# Copy_of_MCU_64.net
KiCad netlist of a schematic drawn in Altium Designer
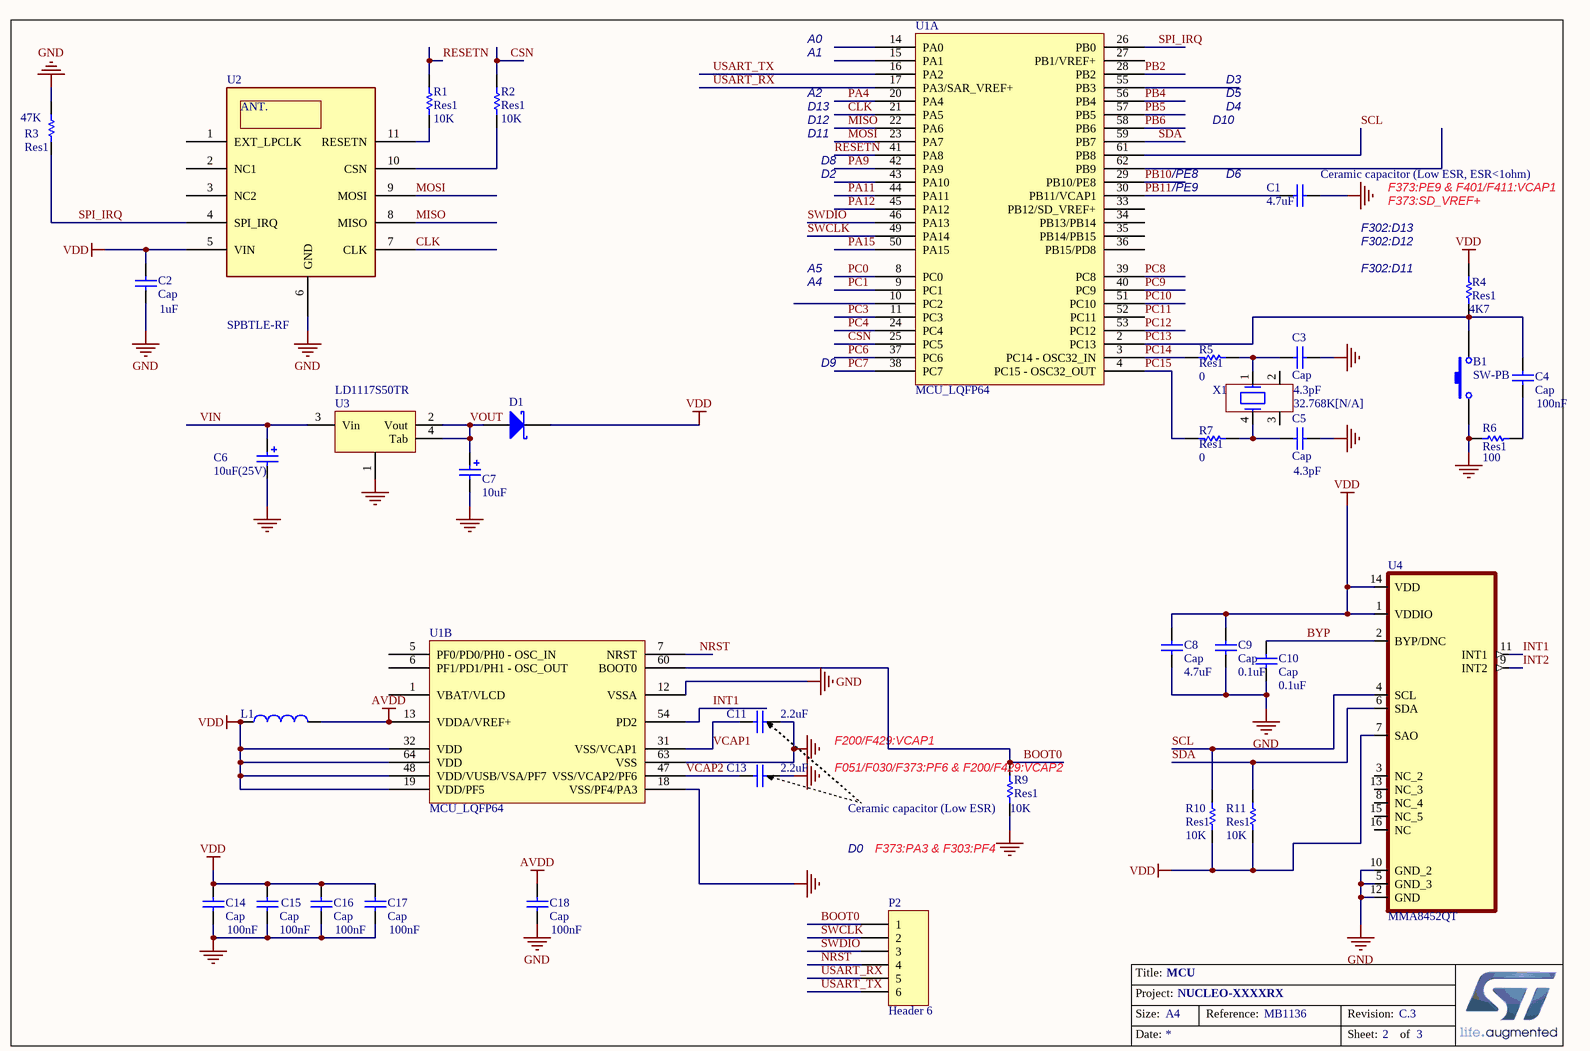
[diagram p0: Copy of MCU_64.SchDoc]

(export (version "E")
  (design (tool "Eeschema 10.0.6"))
  (components
    (comp (ref "B1")
      (value "SW-PB")
      (footprint "SPST-2")
      (description "Switch")
      (fields (field (name "PUBLISHER") "Altium Limited"))
      (libsource (lib "Gen_Devices") (part "SW-PB"))
    )
    (comp (ref "C1")
      (value "4.7uF")
      (footprint "TAN-A")
      (description "Capacitor,4.7uF,25V, X7R,10%,1206,YAGEO")
      (libsource (lib "MCD_TOOLS") (part "Cap_2.2uF_X7R_10%_0805"))
    )
    (comp (ref "C2")
      (value "Cap")
      (footprint "0603[IMP]-CAP")
      (description "Capacitor")
      (fields (field (name "ALTIUM_VALUE") "1uF"))
      (libsource (lib "Gen_Devices") (part "Cap"))
    )
    (comp (ref "C3")
      (value "Cap")
      (footprint "0603[IMP]-CAP")
      (description "Capacitor")
      (fields (field (name "ALTIUM_VALUE") "4.3pF"))
      (libsource (lib "Gen_Devices") (part "Cap"))
    )
    (comp (ref "C4")
      (value "Cap")
      (footprint "0603[IMP]-CAP")
      (description "Capacitor")
      (fields (field (name "ALTIUM_VALUE") "100nF"))
      (libsource (lib "Gen_Devices") (part "Cap"))
    )
    (comp (ref "C5")
      (value "Cap")
      (footprint "0603[IMP]-CAP")
      (description "Capacitor")
      (fields (field (name "ALTIUM_VALUE") "4.3pF"))
      (libsource (lib "Gen_Devices") (part "Cap"))
    )
    (comp (ref "C6")
      (value "10uF(25V)")
      (footprint "TAN-B")
      (description "Polarized Capacitor (Radial)")
      (fields (field (name "PUBLISHER") "Altium Limited"))
      (libsource (lib "Gen_Devices") (part "Cap Pol1"))
    )
    (comp (ref "C7")
      (value "10uF")
      (footprint "TAN-A")
      (description "Polarized Capacitor (Radial)")
      (fields (field (name "PUBLISHER") "Altium Limited"))
      (libsource (lib "Gen_Devices") (part "Cap Pol1"))
    )
    (comp (ref "C8")
      (value "Cap")
      (footprint "0603[IMP]-CAP")
      (description "Capacitor")
      (fields (field (name "ALTIUM_VALUE") "4.7uF"))
      (libsource (lib "Gen_Devices") (part "Cap"))
    )
    (comp (ref "C9")
      (value "Cap")
      (footprint "0603[IMP]-CAP")
      (description "Capacitor")
      (fields (field (name "ALTIUM_VALUE") "0.1uF"))
      (libsource (lib "Gen_Devices") (part "Cap"))
    )
    (comp (ref "C10")
      (value "Cap")
      (footprint "0603[IMP]-CAP")
      (description "Capacitor")
      (fields (field (name "ALTIUM_VALUE") "0.1uF"))
      (libsource (lib "Gen_Devices") (part "Cap"))
    )
    (comp (ref "C11")
      (value "2.2uF")
      (footprint "TAN-A")
      (description "Capacitor,2.2uF,16V, X7R,10%,0805,YAGEO")
      (libsource (lib "MCD_TOOLS") (part "Cap_2.2uF_X7R_10%_0805"))
    )
    (comp (ref "C13")
      (value "2.2uF")
      (footprint "TAN-A")
      (description "Capacitor,2.2uF,16V, X7R,10%,0805,YAGEO")
      (libsource (lib "MCD_TOOLS") (part "Cap_2.2uF_X7R_10%_0805"))
    )
    (comp (ref "C14")
      (value "Cap")
      (footprint "0603[IMP]-CAP")
      (description "Capacitor")
      (fields (field (name "ALTIUM_VALUE") "100nF"))
      (libsource (lib "Gen_Devices") (part "Cap"))
    )
    (comp (ref "C15")
      (value "Cap")
      (footprint "0603[IMP]-CAP")
      (description "Capacitor")
      (fields (field (name "ALTIUM_VALUE") "100nF"))
      (libsource (lib "Gen_Devices") (part "Cap"))
    )
    (comp (ref "C16")
      (value "Cap")
      (footprint "0603[IMP]-CAP")
      (description "Capacitor")
      (fields (field (name "ALTIUM_VALUE") "100nF"))
      (libsource (lib "Gen_Devices") (part "Cap"))
    )
    (comp (ref "C17")
      (value "Cap")
      (footprint "0603[IMP]-CAP")
      (description "Capacitor")
      (fields (field (name "ALTIUM_VALUE") "100nF"))
      (libsource (lib "Gen_Devices") (part "Cap"))
    )
    (comp (ref "C18")
      (value "Cap")
      (footprint "0603[IMP]-CAP")
      (description "Capacitor")
      (fields (field (name "ALTIUM_VALUE") "100nF"))
      (libsource (lib "Gen_Devices") (part "Cap"))
    )
    (comp (ref "D1")
      (value "~")
      (footprint "SMB")
      (description "Schottky Diode")
      (fields (field (name "PUBLISHER") "Altium Limited"))
      (libsource (lib "Gen_Devices") (part "D Schottky"))
    )
    (comp (ref "L1")
      (value "~")
      (footprint "0603[IMP]-CAP")
      (description "Inductor")
      (fields (field (name "PUBLISHER") "Altium Limited"))
      (libsource (lib "Miscellaneous Devices") (part "Inductor"))
    )
    (comp (ref "P2")
      (value "Header 6")
      (footprint "HDR1X6")
      (description "Header, 6-Pin")
      (fields (field (name "PUBLISHER") "Altium Limited"))
      (libsource (lib "Gen_Connectors") (part "Header 6"))
    )
    (comp (ref "R1")
      (value "Res1")
      (footprint "0603[IMP]-RES")
      (description "Resistor")
      (fields (field (name "ALTIUM_VALUE") "10K") (field (name "PUBLISHER") "Altium Limited"))
      (libsource (lib "Gen_Devices") (part "Res1"))
    )
    (comp (ref "R2")
      (value "Res1")
      (footprint "0603[IMP]-RES")
      (description "Resistor")
      (fields (field (name "ALTIUM_VALUE") "10K") (field (name "PUBLISHER") "Altium Limited"))
      (libsource (lib "Gen_Devices") (part "Res1"))
    )
    (comp (ref "R3")
      (value "Res1")
      (footprint "0603[IMP]-RES")
      (description "Resistor")
      (fields (field (name "ALTIUM_VALUE") "47K") (field (name "PUBLISHER") "Altium Limited"))
      (libsource (lib "Gen_Devices") (part "Res1"))
    )
    (comp (ref "R4")
      (value "Res1")
      (footprint "0603[IMP]-RES")
      (description "Resistor")
      (fields (field (name "ALTIUM_VALUE") "4K7") (field (name "PUBLISHER") "Altium Limited"))
      (libsource (lib "Gen_Devices") (part "Res1"))
    )
    (comp (ref "R5")
      (value "Res1")
      (footprint "0603[IMP]-RES")
      (description "Resistor")
      (fields (field (name "ALTIUM_VALUE") "0") (field (name "PUBLISHER") "Altium Limited"))
      (libsource (lib "Gen_Devices") (part "Res1"))
    )
    (comp (ref "R6")
      (value "Res1")
      (footprint "0603[IMP]-RES")
      (description "Resistor")
      (fields (field (name "ALTIUM_VALUE") "100") (field (name "PUBLISHER") "Altium Limited"))
      (libsource (lib "Gen_Devices") (part "Res1"))
    )
    (comp (ref "R7")
      (value "Res1")
      (footprint "0603[IMP]-RES")
      (description "Resistor")
      (fields (field (name "ALTIUM_VALUE") "0") (field (name "PUBLISHER") "Altium Limited"))
      (libsource (lib "Gen_Devices") (part "Res1"))
    )
    (comp (ref "R9")
      (value "Res1")
      (footprint "0603[IMP]-RES")
      (description "Resistor")
      (fields (field (name "ALTIUM_VALUE") "10K") (field (name "PUBLISHER") "Altium Limited"))
      (libsource (lib "Gen_Devices") (part "Res1"))
    )
    (comp (ref "R10")
      (value "Res1")
      (footprint "0603[IMP]-RES")
      (description "Resistor")
      (fields (field (name "ALTIUM_VALUE") "10K") (field (name "PUBLISHER") "Altium Limited"))
      (libsource (lib "Gen_Devices") (part "Res1"))
    )
    (comp (ref "R11")
      (value "Res1")
      (footprint "0603[IMP]-RES")
      (description "Resistor")
      (fields (field (name "ALTIUM_VALUE") "10K") (field (name "PUBLISHER") "Altium Limited"))
      (libsource (lib "Gen_Devices") (part "Res1"))
    )
    (comp (ref "U1")
      (value "MCU_LQFP64")
      (footprint "LQFP64")
      (libsource (lib "Nucleo_64") (part "MCU_LQFP64"))
    )
    (comp (ref "U2")
      (value "SPBTLE-RF")
      (footprint "SPBTLE-RF")
      (description "Module BlueNRG")
      (libsource (lib "KNOCKLET_BRAC") (part "SPBTLE-RF"))
    )
    (comp (ref "U3")
      (value "LD1117S50TR")
      (footprint "SOT223_N")
      (libsource (lib "Gen_Devices") (part "LD1117"))
    )
    (comp (ref "U4")
      (value "MMA8452QT")
      (footprint "MMA8452QT")
      (libsource (lib "Accelerometres") (part "MMA8452QT"))
    )
    (comp (ref "X1")
      (value "32.768K[N/A]")
      (footprint "Quartz_ABS25")
      (libsource (lib "KNOCKLET_BRAC") (part "MC306"))
    )
  )
  (nets
    (net (code "1") (name "/BOOT0") (class "Default")
      (node (ref "P2") (pin "1") (pinfunction "1_1") (pintype "passive"))
      (node (ref "R9") (pin "1") (pinfunction "1_1") (pintype "passive"))
      (node (ref "U1") (pin "60") (pinfunction "BOOT0_60") (pintype "passive"))
    )
    (net (code "2") (name "/BYP") (class "Default")
      (node (ref "C10") (pin "2") (pinfunction "2_2") (pintype "passive"))
      (node (ref "U4") (pin "2") (pinfunction "BYP/DNC_2") (pintype "passive"))
    )
    (net (code "3") (name "/CLK") (class "Default")
      (node (ref "U1") (pin "21") (pinfunction "PA5_21") (pintype "passive"))
      (node (ref "U2") (pin "7") (pinfunction "CLK_7") (pintype "passive"))
    )
    (net (code "4") (name "/CSN") (class "Default")
      (node (ref "R2") (pin "2") (pinfunction "2_2") (pintype "passive"))
      (node (ref "U1") (pin "25") (pinfunction "PC5_25") (pintype "passive"))
    )
    (net (code "5") (name "/INT1") (class "Default")
      (node (ref "U1") (pin "54") (pinfunction "PD2_54") (pintype "passive"))
      (node (ref "U4") (pin "11") (pinfunction "INT1_11") (pintype "output"))
    )
    (net (code "6") (name "/INT2") (class "Default")
      (node (ref "U4") (pin "9") (pinfunction "INT2_9") (pintype "output"))
    )
    (net (code "7") (name "/MISO") (class "Default")
      (node (ref "U1") (pin "22") (pinfunction "PA6_22") (pintype "passive"))
      (node (ref "U2") (pin "8") (pinfunction "MISO_8") (pintype "passive"))
    )
    (net (code "8") (name "/MOSI") (class "Default")
      (node (ref "U1") (pin "23") (pinfunction "PA7_23") (pintype "passive"))
      (node (ref "U2") (pin "9") (pinfunction "MOSI_9") (pintype "passive"))
    )
    (net (code "9") (name "/NRST") (class "Default")
      (node (ref "P2") (pin "4") (pinfunction "4_4") (pintype "passive"))
      (node (ref "U1") (pin "7") (pinfunction "NRST_7") (pintype "passive"))
    )
    (net (code "10") (name "/PA4") (class "Default")
      (node (ref "U1") (pin "20") (pinfunction "PA4_20") (pintype "passive"))
    )
    (net (code "11") (name "/PA9") (class "Default")
      (node (ref "U1") (pin "42") (pinfunction "PA9_42") (pintype "passive"))
    )
    (net (code "12") (name "/PA11") (class "Default")
      (node (ref "U1") (pin "44") (pinfunction "PA11_44") (pintype "passive"))
    )
    (net (code "13") (name "/PA12") (class "Default")
      (node (ref "U1") (pin "45") (pinfunction "PA12_45") (pintype "passive"))
    )
    (net (code "14") (name "/PA15") (class "Default")
      (node (ref "U1") (pin "50") (pinfunction "PA15_50") (pintype "passive"))
    )
    (net (code "15") (name "/PB2") (class "Default")
      (node (ref "U1") (pin "28") (pinfunction "PB2_28") (pintype "passive"))
    )
    (net (code "16") (name "/PB4") (class "Default")
      (node (ref "U1") (pin "56") (pinfunction "PB4_56") (pintype "passive"))
    )
    (net (code "17") (name "/PB5") (class "Default")
      (node (ref "U1") (pin "57") (pinfunction "PB5_57") (pintype "passive"))
    )
    (net (code "18") (name "/PB6") (class "Default")
      (node (ref "U1") (pin "58") (pinfunction "PB6_58") (pintype "passive"))
    )
    (net (code "19") (name "/PB10") (class "Default")
      (node (ref "U1") (pin "29") (pinfunction "PB10/PE8_29") (pintype "passive"))
    )
    (net (code "20") (name "/PB11") (class "Default")
      (node (ref "C1") (pin "1") (pinfunction "1_1") (pintype "passive"))
      (node (ref "U1") (pin "30") (pinfunction "PB11/VCAP1_30") (pintype "passive"))
    )
    (net (code "21") (name "/PC0") (class "Default")
      (node (ref "U1") (pin "8") (pinfunction "PC0_8") (pintype "passive"))
    )
    (net (code "22") (name "/PC1") (class "Default")
      (node (ref "U1") (pin "9") (pinfunction "PC1_9") (pintype "passive"))
    )
    (net (code "23") (name "/PC3") (class "Default")
      (node (ref "U1") (pin "11") (pinfunction "PC3_11") (pintype "passive"))
    )
    (net (code "24") (name "/PC4") (class "Default")
      (node (ref "U1") (pin "24") (pinfunction "PC4_24") (pintype "passive"))
    )
    (net (code "25") (name "/PC6") (class "Default")
      (node (ref "U1") (pin "37") (pinfunction "PC6_37") (pintype "passive"))
    )
    (net (code "26") (name "/PC7") (class "Default")
      (node (ref "U1") (pin "38") (pinfunction "PC7_38") (pintype "passive"))
    )
    (net (code "27") (name "/PC8") (class "Default")
      (node (ref "U1") (pin "39") (pinfunction "PC8_39") (pintype "passive"))
    )
    (net (code "28") (name "/PC9") (class "Default")
      (node (ref "U1") (pin "40") (pinfunction "PC9_40") (pintype "passive"))
    )
    (net (code "29") (name "/PC10") (class "Default")
      (node (ref "U1") (pin "51") (pinfunction "PC10_51") (pintype "passive"))
    )
    (net (code "30") (name "/PC11") (class "Default")
      (node (ref "U1") (pin "52") (pinfunction "PC11_52") (pintype "passive"))
    )
    (net (code "31") (name "/PC12") (class "Default")
      (node (ref "U1") (pin "53") (pinfunction "PC12_53") (pintype "passive"))
    )
    (net (code "32") (name "/PC13") (class "Default")
      (node (ref "B1") (pin "2") (pinfunction "2_2") (pintype "passive"))
      (node (ref "C4") (pin "2") (pinfunction "2_2") (pintype "passive"))
      (node (ref "R4") (pin "1") (pinfunction "1_1") (pintype "passive"))
      (node (ref "U1") (pin "2") (pinfunction "PC13_2") (pintype "passive"))
    )
    (net (code "33") (name "/PC14") (class "Default")
      (node (ref "R5") (pin "1") (pinfunction "1_1") (pintype "passive"))
      (node (ref "U1") (pin "3") (pinfunction "PC14_-_OSC32_IN_3") (pintype "passive"))
    )
    (net (code "34") (name "/PC15") (class "Default")
      (node (ref "R7") (pin "1") (pinfunction "1_1") (pintype "passive"))
      (node (ref "U1") (pin "4") (pinfunction "PC15_-_OSC32_OUT_4") (pintype "passive"))
    )
    (net (code "35") (name "/RESETN") (class "Default")
      (node (ref "R1") (pin "2") (pinfunction "2_2") (pintype "passive"))
      (node (ref "U1") (pin "41") (pinfunction "PA8_41") (pintype "passive"))
    )
    (net (code "36") (name "/SCL") (class "Default")
      (node (ref "R10") (pin "2") (pinfunction "2_2") (pintype "passive"))
      (node (ref "U1") (pin "61") (pinfunction "PB8_61") (pintype "passive"))
      (node (ref "U4") (pin "4") (pinfunction "SCL_4") (pintype "passive"))
    )
    (net (code "37") (name "/SDA") (class "Default")
      (node (ref "R11") (pin "2") (pinfunction "2_2") (pintype "passive"))
      (node (ref "U1") (pin "59") (pinfunction "PB7_59") (pintype "passive"))
      (node (ref "U4") (pin "6") (pinfunction "SDA_6") (pintype "passive"))
    )
    (net (code "38") (name "/SPI_IRQ") (class "Default")
      (node (ref "R3") (pin "1") (pinfunction "1_1") (pintype "passive"))
      (node (ref "U1") (pin "26") (pinfunction "PB0_26") (pintype "passive"))
      (node (ref "U2") (pin "4") (pinfunction "SPI_IRQ_4") (pintype "passive"))
    )
    (net (code "39") (name "/SWCLK") (class "Default")
      (node (ref "P2") (pin "2") (pinfunction "2_2") (pintype "passive"))
      (node (ref "U1") (pin "49") (pinfunction "PA14_49") (pintype "passive"))
    )
    (net (code "40") (name "/SWDIO") (class "Default")
      (node (ref "P2") (pin "3") (pinfunction "3_3") (pintype "passive"))
      (node (ref "U1") (pin "46") (pinfunction "PA13_46") (pintype "passive"))
    )
    (net (code "41") (name "/USART_RX") (class "Default")
      (node (ref "P2") (pin "5") (pinfunction "5_5") (pintype "passive"))
      (node (ref "U1") (pin "17") (pinfunction "PA3/SAR_VREF+_17") (pintype "passive"))
    )
    (net (code "42") (name "/USART_TX") (class "Default")
      (node (ref "P2") (pin "6") (pinfunction "6_6") (pintype "passive"))
      (node (ref "U1") (pin "16") (pinfunction "PA2_16") (pintype "passive"))
    )
    (net (code "43") (name "/VCAP1") (class "Default")
      (node (ref "C11") (pin "1") (pinfunction "1_1") (pintype "passive"))
      (node (ref "U1") (pin "31") (pinfunction "VSS/VCAP1_31") (pintype "passive"))
    )
    (net (code "44") (name "/VCAP2") (class "Default")
      (node (ref "C13") (pin "1") (pinfunction "1_1") (pintype "passive"))
      (node (ref "U1") (pin "47") (pinfunction "VSS/VCAP2/PF6_47") (pintype "passive"))
    )
    (net (code "45") (name "/VIN") (class "Default")
      (node (ref "C6") (pin "1") (pinfunction "1_1") (pintype "passive"))
      (node (ref "U3") (pin "3") (pinfunction "Vin_3") (pintype "power_in"))
    )
    (net (code "46") (name "/VOUT") (class "Default")
      (node (ref "C7") (pin "1") (pinfunction "1_1") (pintype "passive"))
      (node (ref "D1") (pin "1") (pinfunction "A_1") (pintype "passive"))
      (node (ref "U3") (pin "2") (pinfunction "Vout_2") (pintype "power_in"))
      (node (ref "U3") (pin "4") (pinfunction "Tab_4") (pintype "power_in"))
    )
    (net (code "47") (name "AVDD") (class "Default")
      (node (ref "C18") (pin "1") (pinfunction "1_1") (pintype "passive"))
      (node (ref "L1") (pin "2") (pinfunction "2_2") (pintype "passive"))
      (node (ref "U1") (pin "13") (pinfunction "VDDA/VREF+_13") (pintype "passive"))
    )
    (net (code "48") (name "GND") (class "Default")
      (node (ref "B1") (pin "1") (pinfunction "1_1") (pintype "passive"))
      (node (ref "C1") (pin "2") (pinfunction "2_2") (pintype "passive"))
      (node (ref "C10") (pin "1") (pinfunction "1_1") (pintype "passive"))
      (node (ref "C11") (pin "2") (pinfunction "2_2") (pintype "passive"))
      (node (ref "C13") (pin "2") (pinfunction "2_2") (pintype "passive"))
      (node (ref "C14") (pin "2") (pinfunction "2_2") (pintype "passive"))
      (node (ref "C15") (pin "2") (pinfunction "2_2") (pintype "passive"))
      (node (ref "C16") (pin "2") (pinfunction "2_2") (pintype "passive"))
      (node (ref "C17") (pin "2") (pinfunction "2_2") (pintype "passive"))
      (node (ref "C18") (pin "2") (pinfunction "2_2") (pintype "passive"))
      (node (ref "C2") (pin "1") (pinfunction "1_1") (pintype "passive"))
      (node (ref "C3") (pin "1") (pinfunction "1_1") (pintype "passive"))
      (node (ref "C5") (pin "1") (pinfunction "1_1") (pintype "passive"))
      (node (ref "C6") (pin "2") (pinfunction "2_2") (pintype "passive"))
      (node (ref "C7") (pin "2") (pinfunction "2_2") (pintype "passive"))
      (node (ref "C8") (pin "1") (pinfunction "1_1") (pintype "passive"))
      (node (ref "C9") (pin "1") (pinfunction "1_1") (pintype "passive"))
      (node (ref "R3") (pin "2") (pinfunction "2_2") (pintype "passive"))
      (node (ref "R6") (pin "1") (pinfunction "1_1") (pintype "passive"))
      (node (ref "R9") (pin "2") (pinfunction "2_2") (pintype "passive"))
      (node (ref "U1") (pin "12") (pinfunction "VSSA_12") (pintype "passive"))
      (node (ref "U1") (pin "18") (pinfunction "VSS/PF4/PA3_18") (pintype "passive"))
      (node (ref "U1") (pin "63") (pinfunction "VSS_63") (pintype "passive"))
      (node (ref "U2") (pin "6") (pinfunction "GND_6") (pintype "passive"))
      (node (ref "U3") (pin "1") (pintype "passive"))
      (node (ref "U4") (pin "10") (pinfunction "GND_2_10") (pintype "passive"))
      (node (ref "U4") (pin "12") (pinfunction "GND_12") (pintype "passive"))
      (node (ref "U4") (pin "5") (pinfunction "GND_3_5") (pintype "passive"))
    )
    (net (code "49") (name "Net-(C3-Pad2)") (class "Default")
      (node (ref "C3") (pin "2") (pinfunction "2_2") (pintype "passive"))
      (node (ref "R5") (pin "2") (pinfunction "2_2") (pintype "passive"))
      (node (ref "X1") (pin "1") (pinfunction "1_1") (pintype "passive"))
    )
    (net (code "50") (name "Net-(C4-Pad1)") (class "Default")
      (node (ref "C4") (pin "1") (pinfunction "1_1") (pintype "passive"))
      (node (ref "R6") (pin "2") (pinfunction "2_2") (pintype "passive"))
    )
    (net (code "51") (name "Net-(C5-Pad2)") (class "Default")
      (node (ref "C5") (pin "2") (pinfunction "2_2") (pintype "passive"))
      (node (ref "R7") (pin "2") (pinfunction "2_2") (pintype "passive"))
      (node (ref "X1") (pin "4") (pinfunction "4_4") (pintype "passive"))
    )
    (net (code "52") (name "Net-(U2-CSN)") (class "Default")
      (node (ref "R2") (pin "1") (pinfunction "1_1") (pintype "passive"))
      (node (ref "U2") (pin "10") (pinfunction "CSN_10") (pintype "passive"))
    )
    (net (code "53") (name "Net-(U2-RESETN)") (class "Default")
      (node (ref "R1") (pin "1") (pinfunction "1_1") (pintype "passive"))
      (node (ref "U2") (pin "11") (pinfunction "RESETN_11") (pintype "passive"))
    )
    (net (code "54") (name "VDD") (class "Default")
      (node (ref "C14") (pin "1") (pinfunction "1_1") (pintype "passive"))
      (node (ref "C15") (pin "1") (pinfunction "1_1") (pintype "passive"))
      (node (ref "C16") (pin "1") (pinfunction "1_1") (pintype "passive"))
      (node (ref "C17") (pin "1") (pinfunction "1_1") (pintype "passive"))
      (node (ref "C2") (pin "2") (pinfunction "2_2") (pintype "passive"))
      (node (ref "C8") (pin "2") (pinfunction "2_2") (pintype "passive"))
      (node (ref "C9") (pin "2") (pinfunction "2_2") (pintype "passive"))
      (node (ref "D1") (pin "2") (pinfunction "K_2") (pintype "passive"))
      (node (ref "L1") (pin "1") (pinfunction "1_1") (pintype "passive"))
      (node (ref "R10") (pin "1") (pinfunction "1_1") (pintype "passive"))
      (node (ref "R11") (pin "1") (pinfunction "1_1") (pintype "passive"))
      (node (ref "R4") (pin "2") (pinfunction "2_2") (pintype "passive"))
      (node (ref "U1") (pin "19") (pinfunction "VDD/PF5_19") (pintype "passive"))
      (node (ref "U1") (pin "32") (pinfunction "VDD_32") (pintype "passive"))
      (node (ref "U1") (pin "48") (pinfunction "VDD/VUSB/VSA/PF7_48") (pintype "passive"))
      (node (ref "U1") (pin "64") (pinfunction "VDD_64") (pintype "passive"))
      (node (ref "U2") (pin "5") (pinfunction "VIN_5") (pintype "passive"))
      (node (ref "U4") (pin "1") (pinfunction "VDDIO_1") (pintype "power_in"))
      (node (ref "U4") (pin "14") (pinfunction "VDD_14") (pintype "power_in"))
      (node (ref "U4") (pin "7") (pinfunction "SAO_7") (pintype "passive"))
    )
    (net (code "55") (name "unconnected-(U1A-PA0-Pad14)") (class "Default")
      (node (ref "U1") (pin "14") (pinfunction "PA0_14") (pintype "passive"))
    )
    (net (code "56") (name "unconnected-(U1A-PA1-Pad15)") (class "Default")
      (node (ref "U1") (pin "15") (pinfunction "PA1_15") (pintype "passive"))
    )
    (net (code "57") (name "unconnected-(U1A-PA10-Pad43)") (class "Default")
      (node (ref "U1") (pin "43") (pinfunction "PA10_43") (pintype "passive"))
    )
    (net (code "58") (name "unconnected-(U1A-PB1{slash}VREF+-Pad27)") (class "Default")
      (node (ref "U1") (pin "27") (pinfunction "PB1/VREF+_27") (pintype "passive"))
    )
    (net (code "59") (name "unconnected-(U1A-PB3-Pad55)") (class "Default")
      (node (ref "U1") (pin "55") (pinfunction "PB3_55") (pintype "passive"))
    )
    (net (code "60") (name "unconnected-(U1A-PB9-Pad62)") (class "Default")
      (node (ref "U1") (pin "62") (pinfunction "PB9_62") (pintype "passive"))
    )
    (net (code "61") (name "unconnected-(U1A-PB12{slash}SD_VREF+-Pad33)") (class "Default")
      (node (ref "U1") (pin "33") (pinfunction "PB12/SD_VREF+_33") (pintype "passive"))
    )
    (net (code "62") (name "unconnected-(U1A-PB13{slash}PB14-Pad34)") (class "Default")
      (node (ref "U1") (pin "34") (pinfunction "PB13/PB14_34") (pintype "passive"))
    )
    (net (code "63") (name "unconnected-(U1A-PB14{slash}PB15-Pad35)") (class "Default")
      (node (ref "U1") (pin "35") (pinfunction "PB14/PB15_35") (pintype "passive"))
    )
    (net (code "64") (name "unconnected-(U1A-PB15{slash}PD8-Pad36)") (class "Default")
      (node (ref "U1") (pin "36") (pinfunction "PB15/PD8_36") (pintype "passive"))
    )
    (net (code "65") (name "unconnected-(U1A-PC2-Pad10)") (class "Default")
      (node (ref "U1") (pin "10") (pinfunction "PC2_10") (pintype "passive"))
    )
    (net (code "66") (name "unconnected-(U1B-PF0{slash}PD0{slash}PH0_-_OSC_IN-Pad5)") (class "Default")
      (node (ref "U1") (pin "5") (pinfunction "PF0/PD0/PH0_-_OSC_IN_5") (pintype "passive"))
    )
    (net (code "67") (name "unconnected-(U1B-PF1{slash}PD1{slash}PH1_-_OSC_OUT-Pad6)") (class "Default")
      (node (ref "U1") (pin "6") (pinfunction "PF1/PD1/PH1_-_OSC_OUT_6") (pintype "passive"))
    )
    (net (code "68") (name "unconnected-(U1B-VBAT{slash}VLCD-Pad1)") (class "Default")
      (node (ref "U1") (pin "1") (pinfunction "VBAT/VLCD_1") (pintype "passive"))
    )
    (net (code "69") (name "unconnected-(U2-EXT_LPCLK-Pad1)") (class "Default")
      (node (ref "U2") (pin "1") (pinfunction "EXT_LPCLK_1") (pintype "passive"))
    )
    (net (code "70") (name "unconnected-(U2-NC1-Pad2)") (class "Default")
      (node (ref "U2") (pin "2") (pinfunction "NC1_2") (pintype "passive"))
    )
    (net (code "71") (name "unconnected-(U2-NC2-Pad3)") (class "Default")
      (node (ref "U2") (pin "3") (pinfunction "NC2_3") (pintype "passive"))
    )
    (net (code "72") (name "unconnected-(U4-NC-Pad16)") (class "Default")
      (node (ref "U4") (pin "16") (pinfunction "NC_16") (pintype "passive"))
    )
    (net (code "73") (name "unconnected-(U4-NC_2-Pad3)") (class "Default")
      (node (ref "U4") (pin "3") (pinfunction "NC_2_3") (pintype "passive"))
    )
    (net (code "74") (name "unconnected-(U4-NC_3-Pad13)") (class "Default")
      (node (ref "U4") (pin "13") (pinfunction "NC_3_13") (pintype "passive"))
    )
    (net (code "75") (name "unconnected-(U4-NC_4-Pad8)") (class "Default")
      (node (ref "U4") (pin "8") (pinfunction "NC_4_8") (pintype "passive"))
    )
    (net (code "76") (name "unconnected-(U4-NC_5-Pad15)") (class "Default")
      (node (ref "U4") (pin "15") (pinfunction "NC_5_15") (pintype "passive"))
    )
    (net (code "77") (name "unconnected-(X1-Pad2)") (class "Default")
      (node (ref "X1") (pin "2") (pinfunction "2_2") (pintype "passive"))
    )
    (net (code "78") (name "unconnected-(X1-Pad3)") (class "Default")
      (node (ref "X1") (pin "3") (pinfunction "3_3") (pintype "passive"))
    )
  )
)
